# irisc.net
KiCad netlist of a schematic drawn in EAGLE
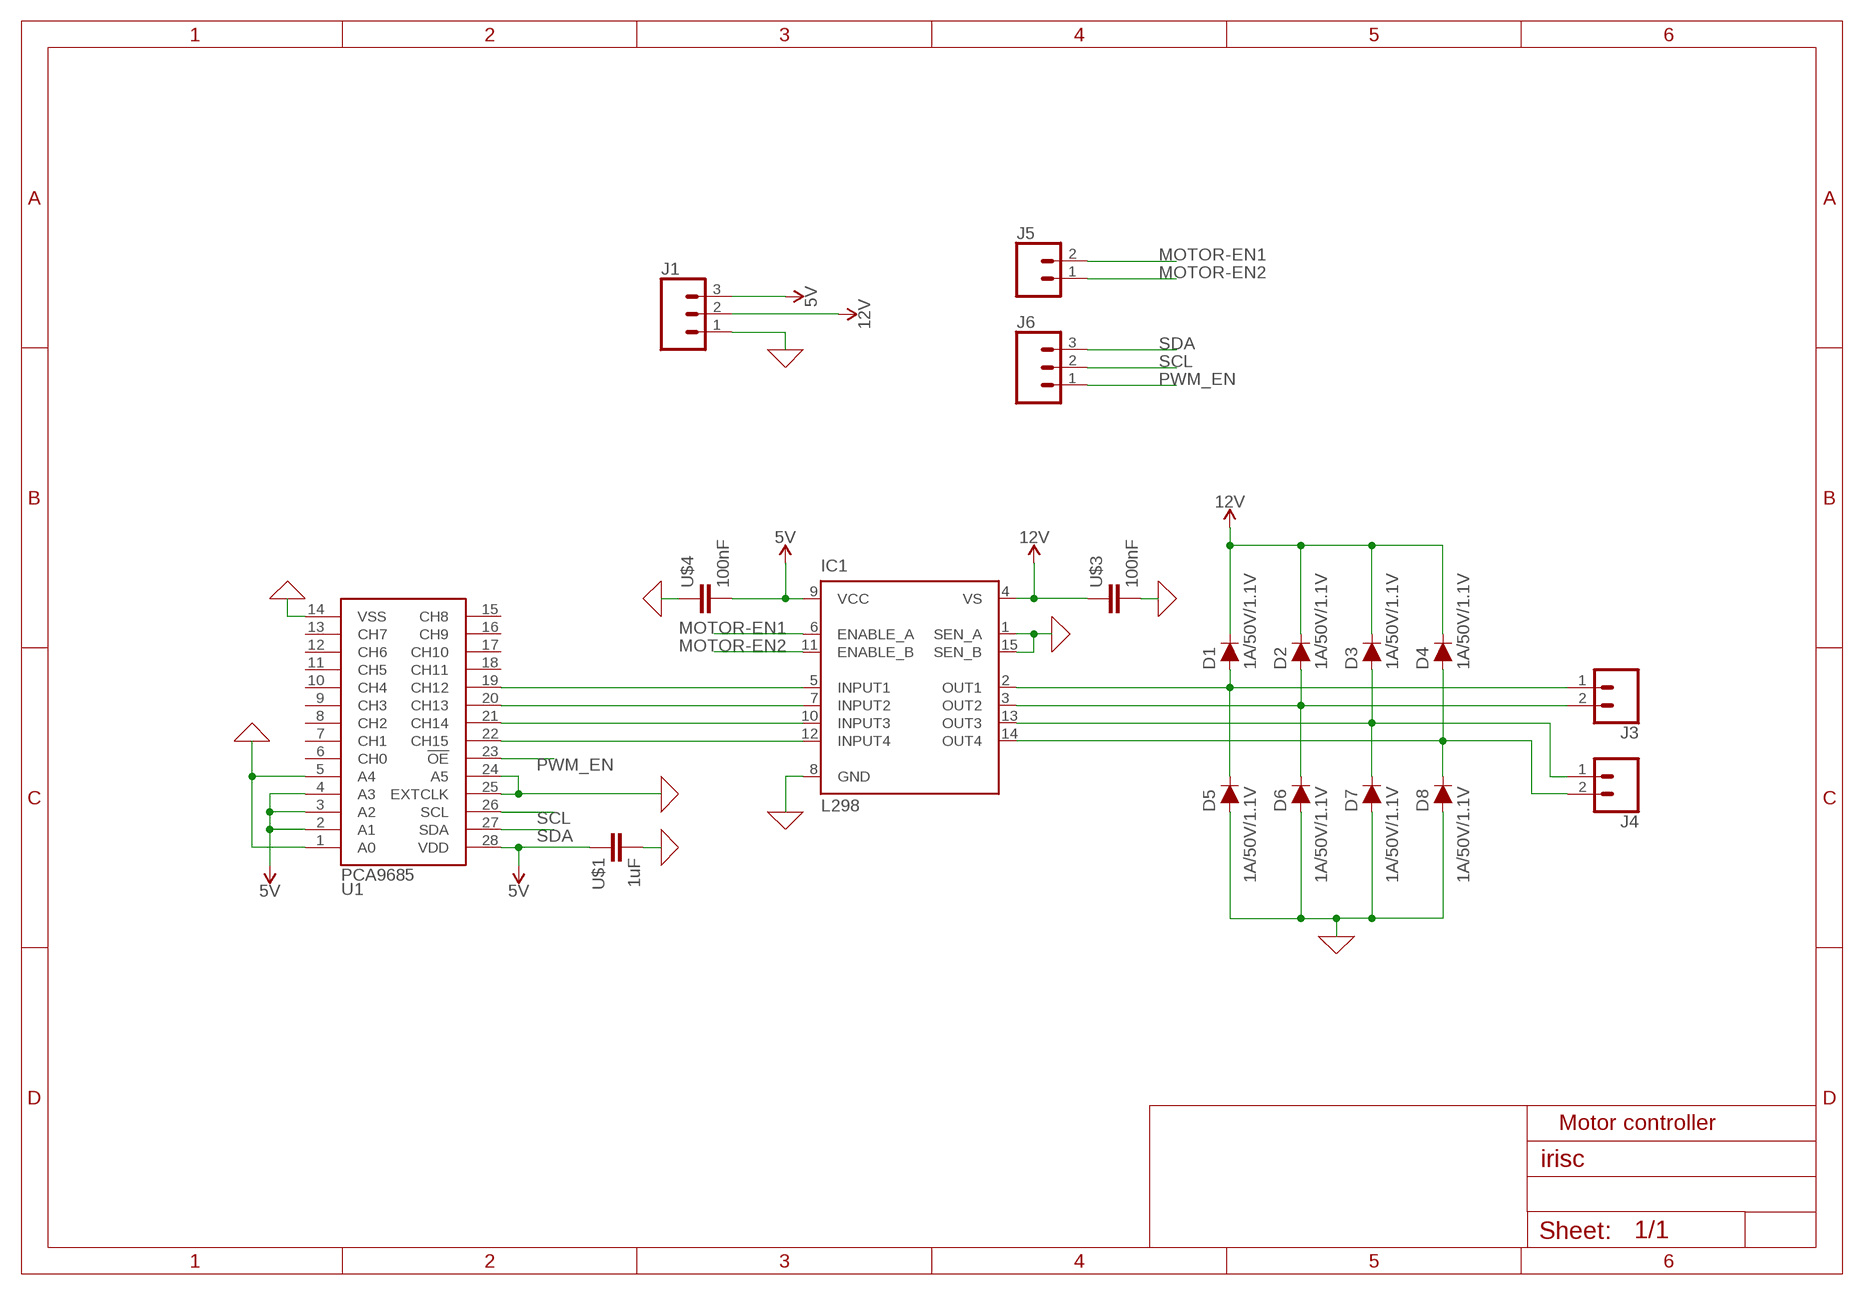
[diagram p0: schematic, sheet 1]

(export (version "E")
  (design (tool "Eeschema 10.0.6"))
  (components
    (comp (ref "D1")
      (value "1A/50V/1.1V")
      (footprint "eagle-import:DIODE-1N4001")
      (libsource (lib "eagle-import") (part "DIODE-PTH"))
    )
    (comp (ref "D2")
      (value "1A/50V/1.1V")
      (footprint "eagle-import:DIODE-1N4001")
      (libsource (lib "eagle-import") (part "DIODE-PTH"))
    )
    (comp (ref "D3")
      (value "1A/50V/1.1V")
      (footprint "eagle-import:DIODE-1N4001")
      (libsource (lib "eagle-import") (part "DIODE-PTH"))
    )
    (comp (ref "D4")
      (value "1A/50V/1.1V")
      (footprint "eagle-import:DIODE-1N4001")
      (libsource (lib "eagle-import") (part "DIODE-PTH"))
    )
    (comp (ref "D5")
      (value "1A/50V/1.1V")
      (footprint "eagle-import:DIODE-1N4001")
      (libsource (lib "eagle-import") (part "DIODE-PTH"))
    )
    (comp (ref "D6")
      (value "1A/50V/1.1V")
      (footprint "eagle-import:DIODE-1N4001")
      (libsource (lib "eagle-import") (part "DIODE-PTH"))
    )
    (comp (ref "D7")
      (value "1A/50V/1.1V")
      (footprint "eagle-import:DIODE-1N4001")
      (libsource (lib "eagle-import") (part "DIODE-PTH"))
    )
    (comp (ref "D8")
      (value "1A/50V/1.1V")
      (footprint "eagle-import:DIODE-1N4001")
      (libsource (lib "eagle-import") (part "DIODE-PTH"))
    )
    (comp (ref "IC1")
      (value "L298")
      (footprint "eagle-import:MULTIWATT-15")
      (fields (field (name "MPN") "L298N") (field (name "SPICEPREFIX") "X"))
      (libsource (lib "eagle-import") (part "L298"))
    )
    (comp (ref "J1")
      (value "CONN_03")
      (footprint "eagle-import:1X03")
      (libsource (lib "eagle-import") (part "CONN_03"))
    )
    (comp (ref "J3")
      (value "CONN_023.5MM")
      (footprint "eagle-import:SCREWTERMINAL-3.5MM-2")
      (libsource (lib "eagle-import") (part "CONN_023.5MM"))
    )
    (comp (ref "J4")
      (value "CONN_023.5MM")
      (footprint "eagle-import:SCREWTERMINAL-3.5MM-2")
      (libsource (lib "eagle-import") (part "CONN_023.5MM"))
    )
    (comp (ref "J5")
      (value "CONN_02")
      (footprint "eagle-import:1X02")
      (libsource (lib "eagle-import") (part "CONN_02"))
    )
    (comp (ref "J6")
      (value "CONN_03")
      (footprint "eagle-import:1X03")
      (libsource (lib "eagle-import") (part "CONN_03"))
    )
    (comp (ref "U$1")
      (value "1uF")
      (footprint "eagle-import:RESC0805_L")
      (libsource (lib "eagle-import") (part "CAPACITOR_0805_L"))
    )
    (comp (ref "U$3")
      (value "100nF")
      (footprint "eagle-import:RESC0603_L")
      (libsource (lib "eagle-import") (part "CAPACITOR_0603_L"))
    )
    (comp (ref "U$4")
      (value "100nF")
      (footprint "eagle-import:RESC0603_L")
      (libsource (lib "eagle-import") (part "CAPACITOR_0603_L"))
    )
    (comp (ref "U1")
      (value "PCA9685")
      (footprint "eagle-import:TSSOP-28_4MM")
      (libsource (lib "eagle-import") (part "PCA9685"))
    )
  )
  (nets
    (net (code "1") (name "/MOTOR-EN1") (class "Default")
      (node (ref "IC1") (pin "6") (pinfunction "ENABLE_A_6") (pintype "input"))
      (node (ref "J5") (pin "2") (pinfunction "2_2") (pintype "passive"))
    )
    (net (code "2") (name "/MOTOR-EN2") (class "Default")
      (node (ref "IC1") (pin "11") (pinfunction "ENABLE_B_11") (pintype "input"))
      (node (ref "J5") (pin "1") (pinfunction "1_1") (pintype "passive"))
    )
    (net (code "3") (name "/PWM_EN") (class "Default")
      (node (ref "J6") (pin "1") (pinfunction "1_1") (pintype "passive"))
      (node (ref "U1") (pin "23") (pinfunction "~{OE}_23") (pintype "bidirectional"))
    )
    (net (code "4") (name "/SCL") (class "Default")
      (node (ref "J6") (pin "2") (pinfunction "2_2") (pintype "passive"))
      (node (ref "U1") (pin "26") (pinfunction "SCL_26") (pintype "bidirectional"))
    )
    (net (code "5") (name "/SDA") (class "Default")
      (node (ref "J6") (pin "3") (pinfunction "3_3") (pintype "passive"))
      (node (ref "U1") (pin "27") (pinfunction "SDA_27") (pintype "bidirectional"))
    )
    (net (code "6") (name "5V") (class "Default")
      (node (ref "IC1") (pin "9") (pinfunction "VCC_9") (pintype "power_in"))
      (node (ref "J1") (pin "3") (pinfunction "3_3") (pintype "passive"))
      (node (ref "U$1") (pin "1") (pinfunction "1_1") (pintype "passive"))
      (node (ref "U$4") (pin "2") (pinfunction "2_2") (pintype "passive"))
      (node (ref "U1") (pin "2") (pinfunction "A1_2") (pintype "bidirectional"))
      (node (ref "U1") (pin "28") (pinfunction "VDD_28") (pintype "bidirectional"))
      (node (ref "U1") (pin "3") (pinfunction "A2_3") (pintype "bidirectional"))
      (node (ref "U1") (pin "4") (pinfunction "A3_4") (pintype "bidirectional"))
    )
    (net (code "7") (name "12V") (class "Default")
      (node (ref "D1") (pin "C") (pinfunction "C_C") (pintype "passive"))
      (node (ref "D2") (pin "C") (pinfunction "C_C") (pintype "passive"))
      (node (ref "D3") (pin "C") (pinfunction "C_C") (pintype "passive"))
      (node (ref "D4") (pin "C") (pinfunction "C_C") (pintype "passive"))
      (node (ref "IC1") (pin "4") (pinfunction "VS_4") (pintype "power_in"))
      (node (ref "J1") (pin "2") (pinfunction "2_2") (pintype "passive"))
      (node (ref "U$3") (pin "1") (pinfunction "1_1") (pintype "passive"))
    )
    (net (code "8") (name "GND") (class "Default")
      (node (ref "D5") (pin "A") (pinfunction "A_A") (pintype "passive"))
      (node (ref "D6") (pin "A") (pinfunction "A_A") (pintype "passive"))
      (node (ref "D7") (pin "A") (pinfunction "A_A") (pintype "passive"))
      (node (ref "D8") (pin "A") (pinfunction "A_A") (pintype "passive"))
      (node (ref "IC1") (pin "1") (pinfunction "SEN_A_1") (pintype "input"))
      (node (ref "IC1") (pin "15") (pinfunction "SEN_B_15") (pintype "input"))
      (node (ref "IC1") (pin "8") (pinfunction "GND_8") (pintype "power_in"))
      (node (ref "J1") (pin "1") (pinfunction "1_1") (pintype "passive"))
      (node (ref "U$1") (pin "2") (pinfunction "2_2") (pintype "passive"))
      (node (ref "U$3") (pin "2") (pinfunction "2_2") (pintype "passive"))
      (node (ref "U$4") (pin "1") (pinfunction "1_1") (pintype "passive"))
      (node (ref "U1") (pin "1") (pinfunction "A0_1") (pintype "bidirectional"))
      (node (ref "U1") (pin "14") (pinfunction "VSS_14") (pintype "bidirectional"))
      (node (ref "U1") (pin "24") (pinfunction "A5_24") (pintype "bidirectional"))
      (node (ref "U1") (pin "25") (pinfunction "EXTCLK_25") (pintype "bidirectional"))
      (node (ref "U1") (pin "5") (pinfunction "A4_5") (pintype "bidirectional"))
    )
    (net (code "9") (name "Net-(IC1-INPUT1)") (class "Default")
      (node (ref "IC1") (pin "5") (pinfunction "INPUT1_5") (pintype "input"))
      (node (ref "U1") (pin "19") (pinfunction "CH12_19") (pintype "bidirectional"))
    )
    (net (code "10") (name "Net-(IC1-INPUT2)") (class "Default")
      (node (ref "IC1") (pin "7") (pinfunction "INPUT2_7") (pintype "input"))
      (node (ref "U1") (pin "20") (pinfunction "CH13_20") (pintype "bidirectional"))
    )
    (net (code "11") (name "Net-(IC1-INPUT3)") (class "Default")
      (node (ref "IC1") (pin "10") (pinfunction "INPUT3_10") (pintype "input"))
      (node (ref "U1") (pin "21") (pinfunction "CH14_21") (pintype "bidirectional"))
    )
    (net (code "12") (name "Net-(IC1-INPUT4)") (class "Default")
      (node (ref "IC1") (pin "12") (pinfunction "INPUT4_12") (pintype "input"))
      (node (ref "U1") (pin "22") (pinfunction "CH15_22") (pintype "bidirectional"))
    )
    (net (code "13") (name "Net-(IC1-OUT1)") (class "Default")
      (node (ref "D1") (pin "A") (pinfunction "A_A") (pintype "passive"))
      (node (ref "D5") (pin "C") (pinfunction "C_C") (pintype "passive"))
      (node (ref "IC1") (pin "2") (pinfunction "OUT1_2") (pintype "output"))
      (node (ref "J3") (pin "1") (pinfunction "1_1") (pintype "passive"))
    )
    (net (code "14") (name "Net-(IC1-OUT2)") (class "Default")
      (node (ref "D2") (pin "A") (pinfunction "A_A") (pintype "passive"))
      (node (ref "D6") (pin "C") (pinfunction "C_C") (pintype "passive"))
      (node (ref "IC1") (pin "3") (pinfunction "OUT2_3") (pintype "output"))
      (node (ref "J3") (pin "2") (pinfunction "2_2") (pintype "passive"))
    )
    (net (code "15") (name "Net-(IC1-OUT3)") (class "Default")
      (node (ref "D3") (pin "A") (pinfunction "A_A") (pintype "passive"))
      (node (ref "D7") (pin "C") (pinfunction "C_C") (pintype "passive"))
      (node (ref "IC1") (pin "13") (pinfunction "OUT3_13") (pintype "output"))
      (node (ref "J4") (pin "1") (pinfunction "1_1") (pintype "passive"))
    )
    (net (code "16") (name "Net-(IC1-OUT4)") (class "Default")
      (node (ref "D4") (pin "A") (pinfunction "A_A") (pintype "passive"))
      (node (ref "D8") (pin "C") (pinfunction "C_C") (pintype "passive"))
      (node (ref "IC1") (pin "14") (pinfunction "OUT4_14") (pintype "output"))
      (node (ref "J4") (pin "2") (pinfunction "2_2") (pintype "passive"))
    )
    (net (code "17") (name "unconnected-(U1-CH0-Pad6)") (class "Default")
      (node (ref "U1") (pin "6") (pinfunction "CH0_6") (pintype "bidirectional"))
    )
    (net (code "18") (name "unconnected-(U1-CH1-Pad7)") (class "Default")
      (node (ref "U1") (pin "7") (pinfunction "CH1_7") (pintype "bidirectional"))
    )
    (net (code "19") (name "unconnected-(U1-CH2-Pad8)") (class "Default")
      (node (ref "U1") (pin "8") (pinfunction "CH2_8") (pintype "bidirectional"))
    )
    (net (code "20") (name "unconnected-(U1-CH3-Pad9)") (class "Default")
      (node (ref "U1") (pin "9") (pinfunction "CH3_9") (pintype "bidirectional"))
    )
    (net (code "21") (name "unconnected-(U1-CH4-Pad10)") (class "Default")
      (node (ref "U1") (pin "10") (pinfunction "CH4_10") (pintype "bidirectional"))
    )
    (net (code "22") (name "unconnected-(U1-CH5-Pad11)") (class "Default")
      (node (ref "U1") (pin "11") (pinfunction "CH5_11") (pintype "bidirectional"))
    )
    (net (code "23") (name "unconnected-(U1-CH6-Pad12)") (class "Default")
      (node (ref "U1") (pin "12") (pinfunction "CH6_12") (pintype "bidirectional"))
    )
    (net (code "24") (name "unconnected-(U1-CH7-Pad13)") (class "Default")
      (node (ref "U1") (pin "13") (pinfunction "CH7_13") (pintype "bidirectional"))
    )
    (net (code "25") (name "unconnected-(U1-CH8-Pad15)") (class "Default")
      (node (ref "U1") (pin "15") (pinfunction "CH8_15") (pintype "bidirectional"))
    )
    (net (code "26") (name "unconnected-(U1-CH9-Pad16)") (class "Default")
      (node (ref "U1") (pin "16") (pinfunction "CH9_16") (pintype "bidirectional"))
    )
    (net (code "27") (name "unconnected-(U1-CH10-Pad17)") (class "Default")
      (node (ref "U1") (pin "17") (pinfunction "CH10_17") (pintype "bidirectional"))
    )
    (net (code "28") (name "unconnected-(U1-CH11-Pad18)") (class "Default")
      (node (ref "U1") (pin "18") (pinfunction "CH11_18") (pintype "bidirectional"))
    )
  )
)
